# STM32ZET6.net
KiCad netlist of a schematic drawn in Altium Designer
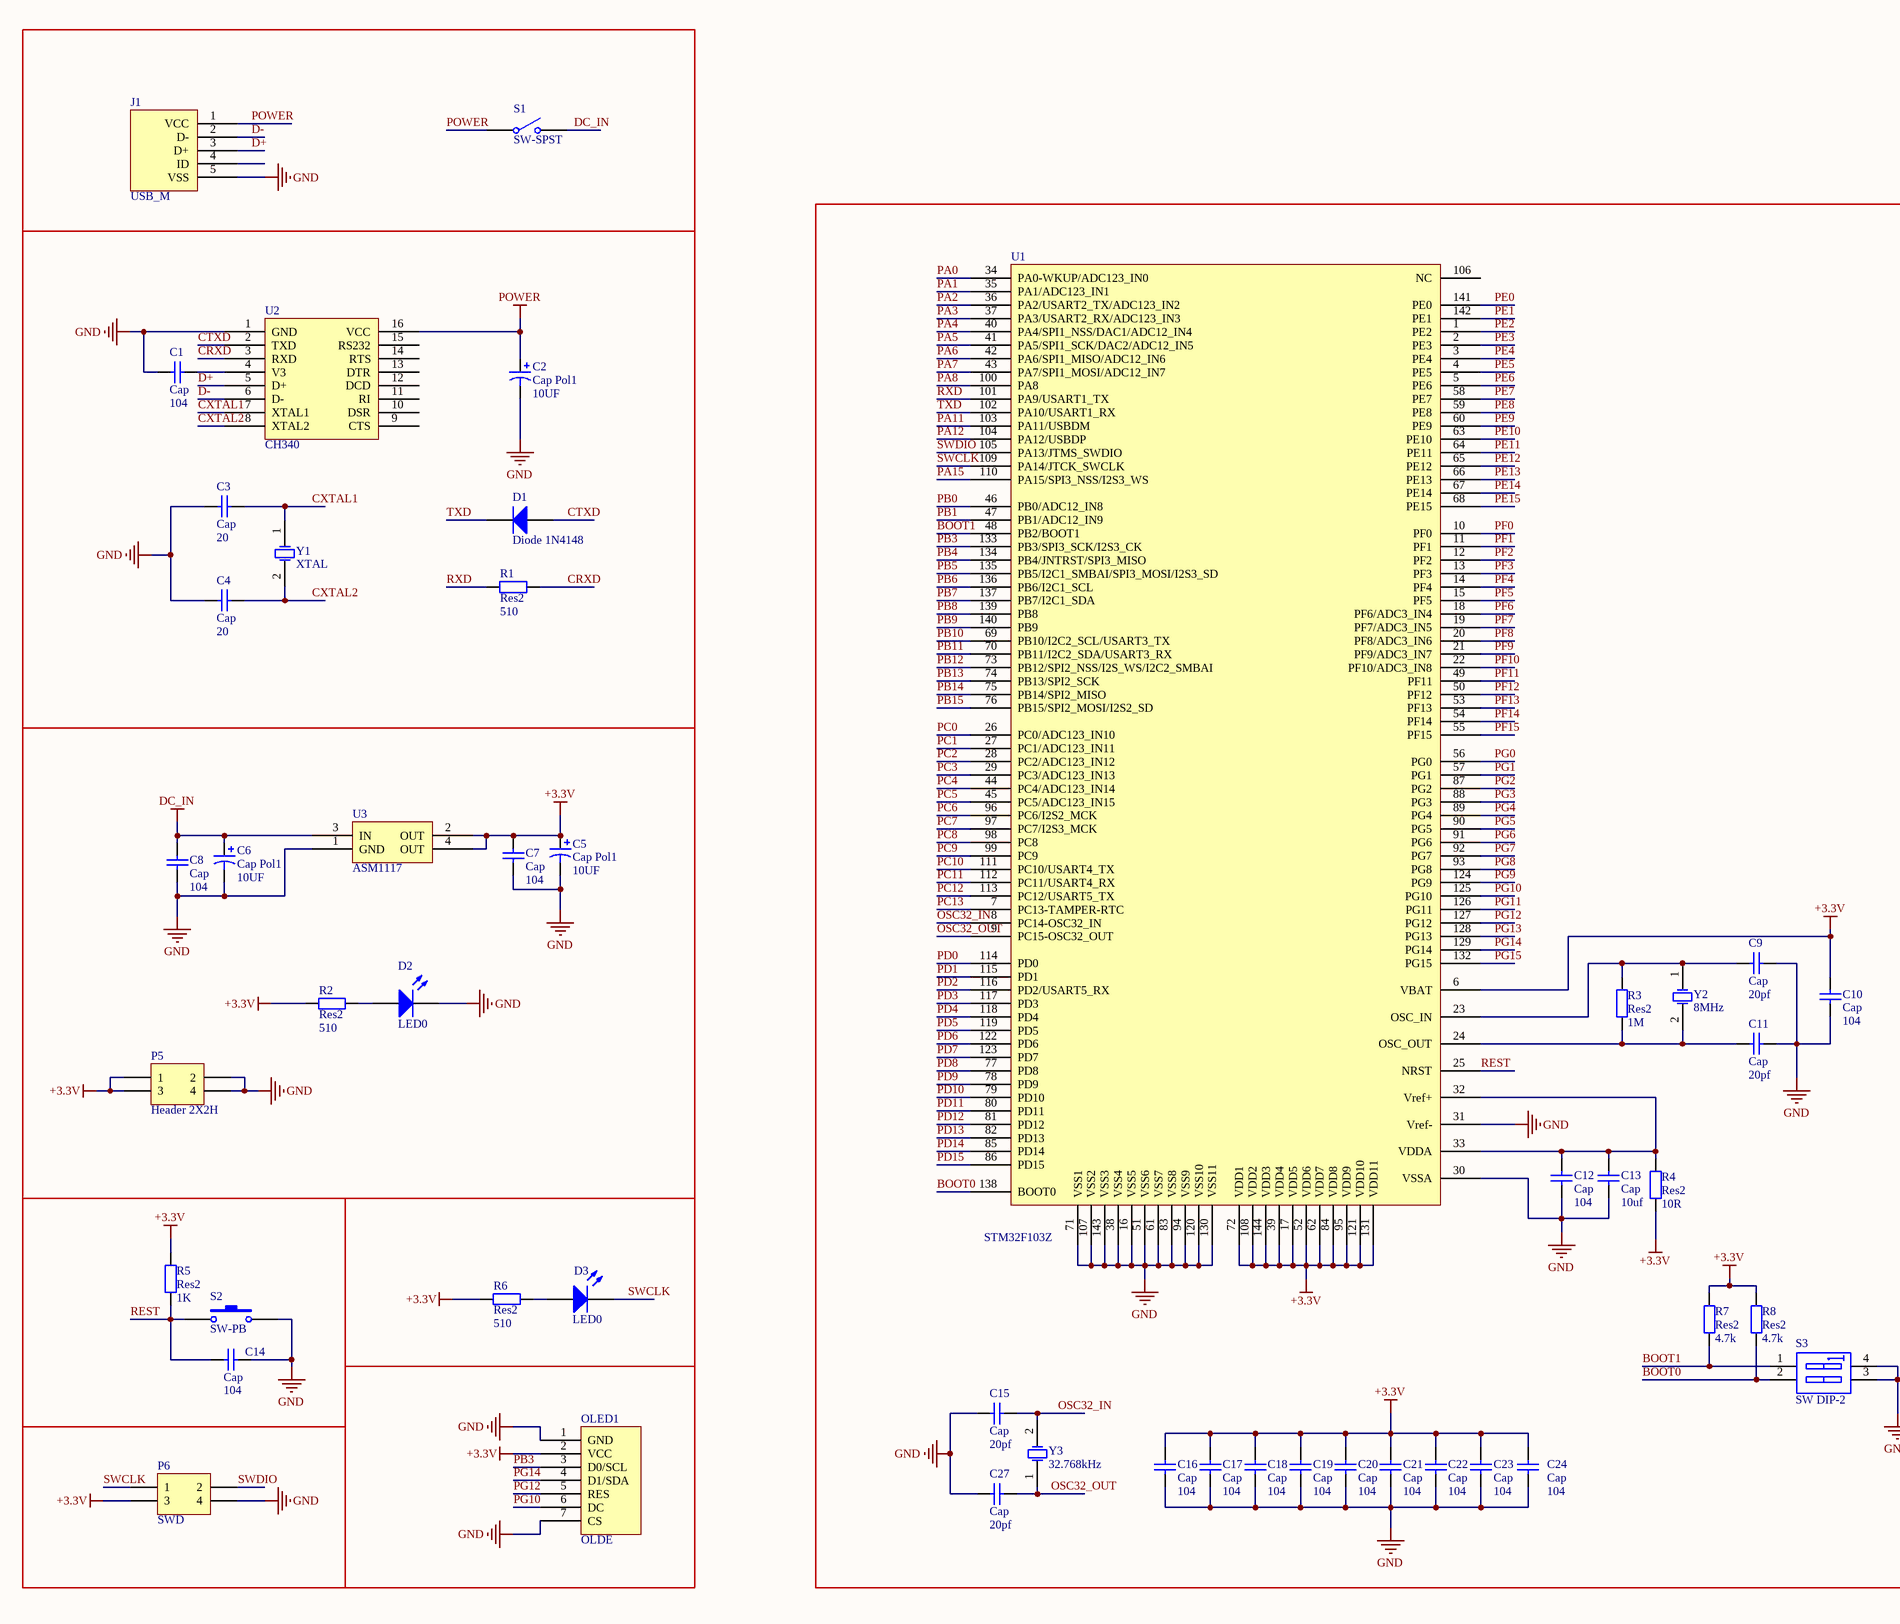
[diagram p0: STM32ZET6最小系统板.SchDoc, left]
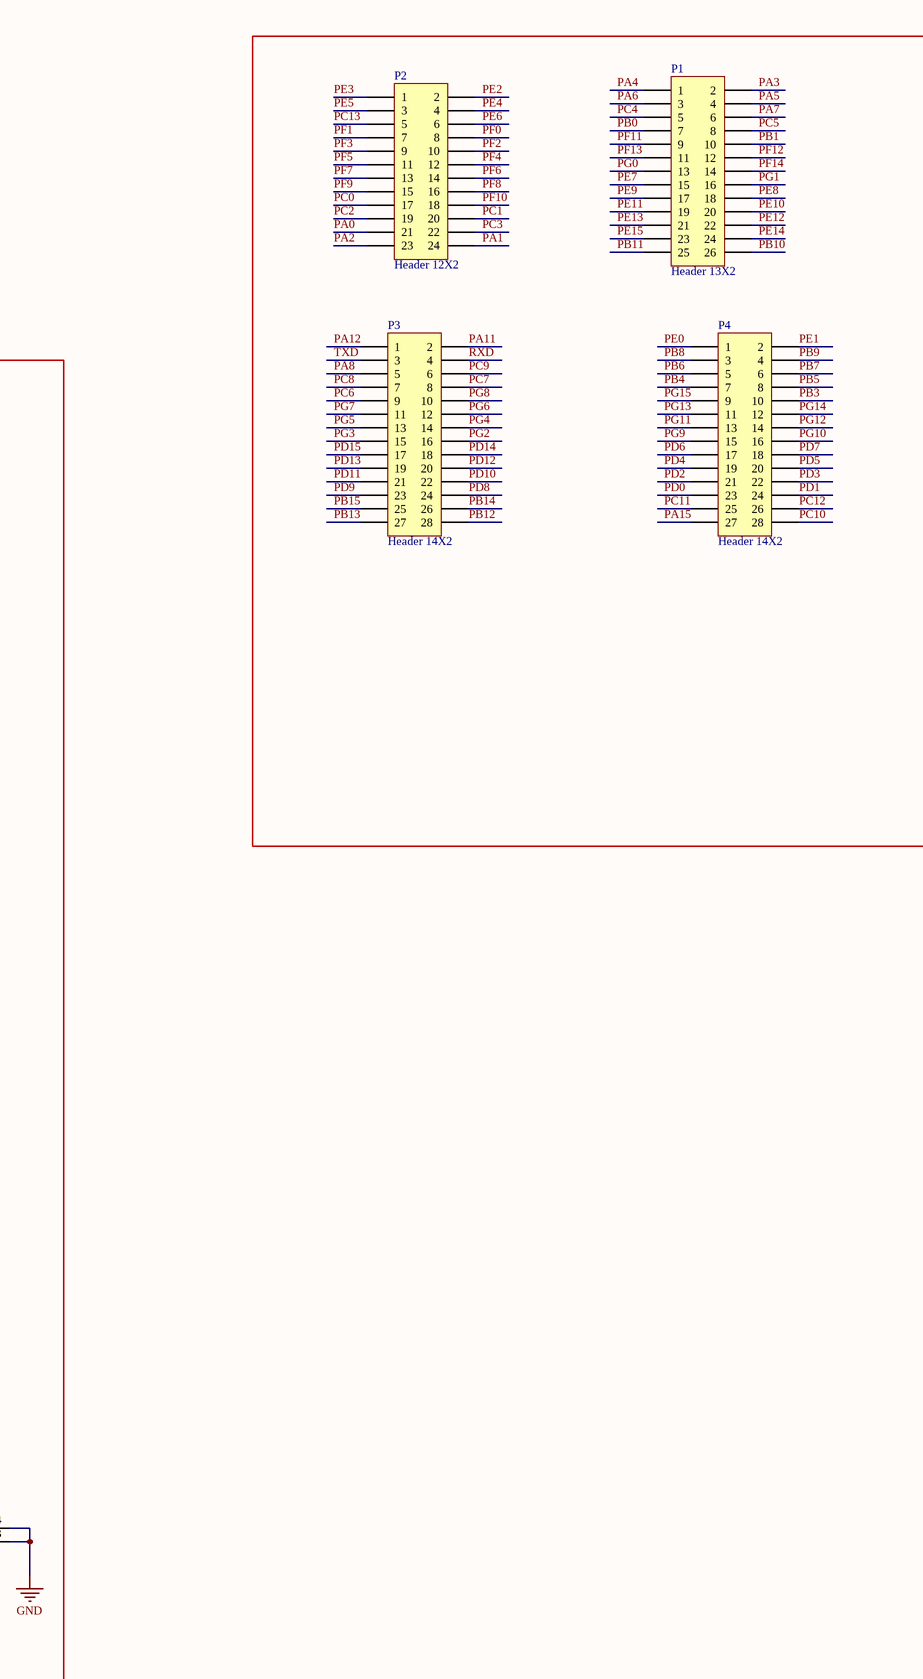
[diagram p1: STM32ZET6最小系统板.SchDoc, right]

(export (version "E")
  (design (tool "Eeschema 10.0.6"))
  (components
    (comp (ref "C1")
      (value "Cap")
      (footprint "C-0805")
      (description "Capacitor")
      (fields (field (name "ALTIUM_VALUE") "104") (field (name "PUBLISHER") "Altium Limited"))
      (libsource (lib "Miscellaneous Devices") (part "Cap"))
    )
    (comp (ref "C2")
      (value "Cap Pol1")
      (footprint "C1206")
      (description "Polarized Capacitor (Radial)")
      (fields (field (name "ALTIUM_VALUE") "10UF") (field (name "PUBLISHER") "Altium Limited"))
      (libsource (lib "Miscellaneous Devices") (part "Cap Pol1"))
    )
    (comp (ref "C3")
      (value "Cap")
      (footprint "C-0805")
      (description "Capacitor")
      (fields (field (name "ALTIUM_VALUE") "20") (field (name "PUBLISHER") "Altium Limited"))
      (libsource (lib "Miscellaneous Devices") (part "Cap"))
    )
    (comp (ref "C4")
      (value "Cap")
      (footprint "C-0805")
      (description "Capacitor")
      (fields (field (name "ALTIUM_VALUE") "20") (field (name "PUBLISHER") "Altium Limited"))
      (libsource (lib "Miscellaneous Devices") (part "Cap"))
    )
    (comp (ref "C5")
      (value "Cap Pol1")
      (footprint "C1206")
      (description "Polarized Capacitor (Radial)")
      (fields (field (name "ALTIUM_VALUE") "10UF") (field (name "PUBLISHER") "Altium Limited"))
      (libsource (lib "Miscellaneous Devices") (part "Cap Pol1"))
    )
    (comp (ref "C6")
      (value "Cap Pol1")
      (footprint "C1206")
      (description "Polarized Capacitor (Radial)")
      (fields (field (name "ALTIUM_VALUE") "10UF") (field (name "PUBLISHER") "Altium Limited"))
      (libsource (lib "Miscellaneous Devices") (part "Cap Pol1"))
    )
    (comp (ref "C7")
      (value "Cap")
      (footprint "C-0805")
      (description "Capacitor")
      (fields (field (name "ALTIUM_VALUE") "104") (field (name "PUBLISHER") "Altium Limited"))
      (libsource (lib "Miscellaneous Devices") (part "Cap"))
    )
    (comp (ref "C8")
      (value "Cap")
      (footprint "C-0805")
      (description "Capacitor")
      (fields (field (name "ALTIUM_VALUE") "104") (field (name "PUBLISHER") "Altium Limited"))
      (libsource (lib "Miscellaneous Devices") (part "Cap"))
    )
    (comp (ref "C9")
      (value "Cap")
      (footprint "C-0805")
      (description "Capacitor")
      (fields (field (name "ALTIUM_VALUE") "20pf") (field (name "PUBLISHER") "Altium Limited"))
      (libsource (lib "Miscellaneous Devices") (part "Cap"))
    )
    (comp (ref "C10")
      (value "Cap")
      (footprint "C-0805")
      (description "Capacitor")
      (fields (field (name "ALTIUM_VALUE") "104") (field (name "PUBLISHER") "Altium Limited"))
      (libsource (lib "Miscellaneous Devices") (part "Cap"))
    )
    (comp (ref "C11")
      (value "Cap")
      (footprint "C-0805")
      (description "Capacitor")
      (fields (field (name "ALTIUM_VALUE") "20pf") (field (name "PUBLISHER") "Altium Limited"))
      (libsource (lib "Miscellaneous Devices") (part "Cap"))
    )
    (comp (ref "C12")
      (value "Cap")
      (footprint "C-0805")
      (description "Capacitor")
      (fields (field (name "ALTIUM_VALUE") "104") (field (name "PUBLISHER") "Altium Limited"))
      (libsource (lib "Miscellaneous Devices") (part "Cap"))
    )
    (comp (ref "C13")
      (value "Cap")
      (footprint "C-0805")
      (description "Capacitor")
      (fields (field (name "ALTIUM_VALUE") "10uf") (field (name "PUBLISHER") "Altium Limited"))
      (libsource (lib "Miscellaneous Devices") (part "Cap"))
    )
    (comp (ref "C14")
      (value "Cap")
      (footprint "C-0805")
      (description "Capacitor")
      (fields (field (name "ALTIUM_VALUE") "104") (field (name "PUBLISHER") "Altium Limited"))
      (libsource (lib "Miscellaneous Devices") (part "Cap"))
    )
    (comp (ref "C15")
      (value "Cap")
      (footprint "C-0805")
      (description "Capacitor")
      (fields (field (name "ALTIUM_VALUE") "20pf") (field (name "PUBLISHER") "Altium Limited"))
      (libsource (lib "Miscellaneous Devices") (part "Cap"))
    )
    (comp (ref "C16")
      (value "Cap")
      (footprint "C-0805")
      (description "Capacitor")
      (fields (field (name "ALTIUM_VALUE") "104") (field (name "PUBLISHER") "Altium Limited"))
      (libsource (lib "Miscellaneous Devices") (part "Cap"))
    )
    (comp (ref "C17")
      (value "Cap")
      (footprint "C-0805")
      (description "Capacitor")
      (fields (field (name "ALTIUM_VALUE") "104") (field (name "PUBLISHER") "Altium Limited"))
      (libsource (lib "Miscellaneous Devices") (part "Cap"))
    )
    (comp (ref "C18")
      (value "Cap")
      (footprint "C-0805")
      (description "Capacitor")
      (fields (field (name "ALTIUM_VALUE") "104") (field (name "PUBLISHER") "Altium Limited"))
      (libsource (lib "Miscellaneous Devices") (part "Cap"))
    )
    (comp (ref "C19")
      (value "Cap")
      (footprint "C-0805")
      (description "Capacitor")
      (fields (field (name "ALTIUM_VALUE") "104") (field (name "PUBLISHER") "Altium Limited"))
      (libsource (lib "Miscellaneous Devices") (part "Cap"))
    )
    (comp (ref "C20")
      (value "Cap")
      (footprint "C-0805")
      (description "Capacitor")
      (fields (field (name "ALTIUM_VALUE") "104") (field (name "PUBLISHER") "Altium Limited"))
      (libsource (lib "Miscellaneous Devices") (part "Cap"))
    )
    (comp (ref "C21")
      (value "Cap")
      (footprint "C-0805")
      (description "Capacitor")
      (fields (field (name "ALTIUM_VALUE") "104") (field (name "PUBLISHER") "Altium Limited"))
      (libsource (lib "Miscellaneous Devices") (part "Cap"))
    )
    (comp (ref "C22")
      (value "Cap")
      (footprint "C-0805")
      (description "Capacitor")
      (fields (field (name "ALTIUM_VALUE") "104") (field (name "PUBLISHER") "Altium Limited"))
      (libsource (lib "Miscellaneous Devices") (part "Cap"))
    )
    (comp (ref "C23")
      (value "Cap")
      (footprint "C-0805")
      (description "Capacitor")
      (fields (field (name "ALTIUM_VALUE") "104") (field (name "PUBLISHER") "Altium Limited"))
      (libsource (lib "Miscellaneous Devices") (part "Cap"))
    )
    (comp (ref "C24")
      (value "Cap")
      (footprint "C-0805")
      (description "Capacitor")
      (fields (field (name "ALTIUM_VALUE") "104") (field (name "PUBLISHER") "Altium Limited"))
      (libsource (lib "Miscellaneous Devices") (part "Cap"))
    )
    (comp (ref "C27")
      (value "Cap")
      (footprint "C-0805")
      (description "Capacitor")
      (fields (field (name "ALTIUM_VALUE") "20pf") (field (name "PUBLISHER") "Altium Limited"))
      (libsource (lib "Miscellaneous Devices") (part "Cap"))
    )
    (comp (ref "D1")
      (value "Diode 1N4148")
      (footprint "SOT-123")
      (description "1 Amp General Purpose Rectifier")
      (fields (field (name "PUBLISHER") "Altium Limited"))
      (libsource (lib "Miscellaneous Devices") (part "Diode 1N4006"))
    )
    (comp (ref "D2")
      (value "LED0")
      (footprint "LED_0805")
      (description "Typical INFRARED GaAs LED")
      (fields (field (name "PUBLISHER") "Altium Limited"))
      (libsource (lib "Miscellaneous Devices") (part "LED0"))
    )
    (comp (ref "D3")
      (value "LED0")
      (footprint "LED_0805")
      (description "Typical INFRARED GaAs LED")
      (fields (field (name "PUBLISHER") "Altium Limited"))
      (libsource (lib "Miscellaneous Devices") (part "LED0"))
    )
    (comp (ref "J1")
      (value "USB_M")
      (footprint "USB_MICRO")
      (description "MicroUSB接口")
      (libsource (lib "常用封装") (part "USB_M"))
    )
    (comp (ref "OLED1") (value "OLDE") (footprint "HDR1X7") (libsource (lib "常用封装") (part "OLED-0.96寸")))
    (comp (ref "P1")
      (value "Header 13X2")
      (footprint "HDR2X13")
      (description "Header, 13-Pin, Dual row")
      (fields (field (name "PUBLISHER") "Altium Limited"))
      (libsource (lib "Miscellaneous Connectors") (part "Header 13X2"))
    )
    (comp (ref "P2")
      (value "Header 12X2")
      (footprint "HDR2X12")
      (description "Header, 12-Pin, Dual row")
      (fields (field (name "PUBLISHER") "Altium Limited"))
      (libsource (lib "Miscellaneous Connectors") (part "Header 12X2"))
    )
    (comp (ref "P3")
      (value "Header 14X2")
      (footprint "HDR2X14")
      (description "Header, 14-Pin, Dual row")
      (fields (field (name "PUBLISHER") "Altium Limited"))
      (libsource (lib "Miscellaneous Connectors") (part "Header 14X2"))
    )
    (comp (ref "P4")
      (value "Header 14X2")
      (footprint "HDR2X14")
      (description "Header, 14-Pin, Dual row")
      (fields (field (name "PUBLISHER") "Altium Limited"))
      (libsource (lib "Miscellaneous Connectors") (part "Header 14X2"))
    )
    (comp (ref "P5")
      (value "Header 2X2H")
      (footprint "HDR2X2")
      (description "Header, 2-Pin, Dual row, Right Angle")
      (fields (field (name "PUBLISHER") "Altium Limited"))
      (libsource (lib "Miscellaneous Connectors") (part "Header 2X2H"))
    )
    (comp (ref "P6")
      (value "SWD")
      (footprint "HDR2X2")
      (description "Header, 2-Pin, Dual row")
      (fields (field (name "PUBLISHER") "Altium Limited"))
      (libsource (lib "Miscellaneous Connectors") (part "Header 2X2"))
    )
    (comp (ref "R1")
      (value "Res2")
      (footprint "0805")
      (description "Resistor")
      (fields (field (name "ALTIUM_VALUE") "510") (field (name "PUBLISHER") "Altium Limited"))
      (libsource (lib "") (part "Res2_1"))
    )
    (comp (ref "R2")
      (value "Res2")
      (footprint "0805")
      (description "Resistor")
      (fields (field (name "ALTIUM_VALUE") "510") (field (name "PUBLISHER") "Altium Limited"))
      (libsource (lib "") (part "Res2_1"))
    )
    (comp (ref "R3")
      (value "Res2")
      (footprint "0805")
      (description "Resistor")
      (fields (field (name "ALTIUM_VALUE") "1M") (field (name "PUBLISHER") "Altium Limited"))
      (libsource (lib "Miscellaneous Devices") (part "Res2"))
    )
    (comp (ref "R4")
      (value "Res2")
      (footprint "0805")
      (description "Resistor")
      (fields (field (name "ALTIUM_VALUE") "10R") (field (name "PUBLISHER") "Altium Limited"))
      (libsource (lib "Miscellaneous Devices") (part "Res2"))
    )
    (comp (ref "R5")
      (value "Res2")
      (footprint "0805")
      (description "Resistor")
      (fields (field (name "ALTIUM_VALUE") "1K") (field (name "PUBLISHER") "Altium Limited"))
      (libsource (lib "Miscellaneous Devices") (part "Res2"))
    )
    (comp (ref "R6")
      (value "Res2")
      (footprint "0805")
      (description "Resistor")
      (fields (field (name "ALTIUM_VALUE") "510") (field (name "PUBLISHER") "Altium Limited"))
      (libsource (lib "") (part "Res2_1"))
    )
    (comp (ref "R7")
      (value "Res2")
      (footprint "0805")
      (description "Resistor")
      (fields (field (name "ALTIUM_VALUE") "4.7k") (field (name "PUBLISHER") "Altium Limited"))
      (libsource (lib "Miscellaneous Devices") (part "Res2"))
    )
    (comp (ref "R8")
      (value "Res2")
      (footprint "0805")
      (description "Resistor")
      (fields (field (name "ALTIUM_VALUE") "4.7k") (field (name "PUBLISHER") "Altium Limited"))
      (libsource (lib "Miscellaneous Devices") (part "Res2"))
    )
    (comp (ref "S1")
      (value "SW-SPST")
      (footprint "SW-mini-6pin")
      (description "Single-Pole, Single-Throw Switch")
      (fields (field (name "PUBLISHER") "Altium Limited"))
      (libsource (lib "Miscellaneous Devices") (part "SW-SPST"))
    )
    (comp (ref "S2")
      (value "SW-PB")
      (footprint "贴片开关")
      (description "Switch")
      (fields (field (name "PUBLISHER") "Altium Limited"))
      (libsource (lib "Miscellaneous Devices") (part "SW-PB"))
    )
    (comp (ref "S3")
      (value "SW DIP-2")
      (footprint "SW4_2BIT")
      (description "编码开关")
      (fields (field (name "PUBLISHER") "Altium Limited"))
      (libsource (lib "常用封装") (part "SW DIP-2"))
    )
    (comp (ref "U1")
      (value "STM32F103Z")
      (footprint "TQFP144_N")
      (description "STM32单片机144引脚")
      (libsource (lib "常用封装") (part "STM32F103Z"))
    )
    (comp (ref "U2") (value "CH340") (footprint "SO-16") (libsource (lib "常用封装") (part "CH340")))
    (comp (ref "U3")
      (value "ASM1117")
      (footprint "SOT-223")
      (description "3.3V稳压芯片")
      (libsource (lib "常用封装") (part "ASM1117"))
    )
    (comp (ref "Y1")
      (value "XTAL")
      (footprint "XTAL-HCM49")
      (description "Crystal Oscillator")
      (fields (field (name "PUBLISHER") "Altium Limited"))
      (libsource (lib "Miscellaneous Devices") (part "XTAL"))
    )
    (comp (ref "Y2")
      (value "8MHz")
      (footprint "XTAL-HCM49")
      (description "Crystal Oscillator")
      (fields (field (name "PUBLISHER") "Altium Limited"))
      (libsource (lib "Miscellaneous Devices") (part "XTAL"))
    )
    (comp (ref "Y3")
      (value "32.768kHz")
      (footprint "X-TC")
      (description "Crystal Oscillator")
      (fields (field (name "PUBLISHER") "Altium Limited"))
      (libsource (lib "Miscellaneous Devices") (part "XTAL"))
    )
  )
  (nets
    (net (code "1") (name "+3.3V") (class "Default")
      (node (ref "C10") (pin "2") (pinfunction "2_2") (pintype "passive"))
      (node (ref "C16") (pin "2") (pinfunction "2_2") (pintype "passive"))
      (node (ref "C17") (pin "2") (pinfunction "2_2") (pintype "passive"))
      (node (ref "C18") (pin "2") (pinfunction "2_2") (pintype "passive"))
      (node (ref "C19") (pin "2") (pinfunction "2_2") (pintype "passive"))
      (node (ref "C20") (pin "2") (pinfunction "2_2") (pintype "passive"))
      (node (ref "C21") (pin "2") (pinfunction "2_2") (pintype "passive"))
      (node (ref "C22") (pin "2") (pinfunction "2_2") (pintype "passive"))
      (node (ref "C23") (pin "2") (pinfunction "2_2") (pintype "passive"))
      (node (ref "C24") (pin "2") (pinfunction "2_2") (pintype "passive"))
      (node (ref "C5") (pin "1") (pinfunction "1_1") (pintype "passive"))
      (node (ref "C7") (pin "2") (pinfunction "2_2") (pintype "passive"))
      (node (ref "OLED1") (pin "2") (pinfunction "VCC_2") (pintype "passive"))
      (node (ref "P5") (pin "1") (pinfunction "1_1") (pintype "passive"))
      (node (ref "P5") (pin "3") (pinfunction "3_3") (pintype "passive"))
      (node (ref "P6") (pin "3") (pinfunction "3_3") (pintype "passive"))
      (node (ref "R2") (pin "1") (pinfunction "1_1") (pintype "passive"))
      (node (ref "R4") (pin "1") (pinfunction "1_1") (pintype "passive"))
      (node (ref "R5") (pin "2") (pinfunction "2_2") (pintype "passive"))
      (node (ref "R6") (pin "1") (pinfunction "1_1") (pintype "passive"))
      (node (ref "R7") (pin "2") (pinfunction "2_2") (pintype "passive"))
      (node (ref "R8") (pin "2") (pinfunction "2_2") (pintype "passive"))
      (node (ref "U1") (pin "108") (pinfunction "VDD2_108") (pintype "passive"))
      (node (ref "U1") (pin "121") (pinfunction "VDD10_121") (pintype "passive"))
      (node (ref "U1") (pin "131") (pinfunction "VDD11_131") (pintype "passive"))
      (node (ref "U1") (pin "144") (pinfunction "VDD3_144") (pintype "passive"))
      (node (ref "U1") (pin "17") (pinfunction "VDD5_17") (pintype "passive"))
      (node (ref "U1") (pin "39") (pinfunction "VDD4_39") (pintype "passive"))
      (node (ref "U1") (pin "52") (pinfunction "VDD6_52") (pintype "passive"))
      (node (ref "U1") (pin "6") (pinfunction "VBAT_6") (pintype "passive"))
      (node (ref "U1") (pin "62") (pinfunction "VDD7_62") (pintype "passive"))
      (node (ref "U1") (pin "72") (pinfunction "VDD1_72") (pintype "passive"))
      (node (ref "U1") (pin "84") (pinfunction "VDD8_84") (pintype "passive"))
      (node (ref "U1") (pin "95") (pinfunction "VDD9_95") (pintype "passive"))
      (node (ref "U3") (pin "2") (pinfunction "OUT_2") (pintype "passive"))
      (node (ref "U3") (pin "4") (pinfunction "OUT_4") (pintype "passive"))
    )
    (net (code "2") (name "/BOOT0") (class "Default")
      (node (ref "R8") (pin "1") (pinfunction "1_1") (pintype "passive"))
      (node (ref "S3") (pin "2") (pinfunction "A2_2") (pintype "passive"))
      (node (ref "U1") (pin "138") (pinfunction "BOOT0_138") (pintype "passive"))
    )
    (net (code "3") (name "/BOOT1") (class "Default")
      (node (ref "R7") (pin "1") (pinfunction "1_1") (pintype "passive"))
      (node (ref "S3") (pin "1") (pinfunction "A1_1") (pintype "passive"))
      (node (ref "U1") (pin "48") (pinfunction "PB2/BOOT1_48") (pintype "passive"))
    )
    (net (code "4") (name "/CRXD") (class "Default")
      (node (ref "R1") (pin "2") (pinfunction "2_2") (pintype "passive"))
      (node (ref "U2") (pin "3") (pinfunction "RXD_3") (pintype "passive"))
    )
    (net (code "5") (name "/CTXD") (class "Default")
      (node (ref "D1") (pin "1") (pinfunction "A_1") (pintype "passive"))
      (node (ref "U2") (pin "2") (pinfunction "TXD_2") (pintype "passive"))
    )
    (net (code "6") (name "/CXTAL1") (class "Default")
      (node (ref "C3") (pin "1") (pinfunction "1_1") (pintype "passive"))
      (node (ref "U2") (pin "7") (pinfunction "XTAL1_7") (pintype "passive"))
      (node (ref "Y1") (pin "1") (pinfunction "OSC1_1") (pintype "passive"))
    )
    (net (code "7") (name "/CXTAL2") (class "Default")
      (node (ref "C4") (pin "1") (pinfunction "1_1") (pintype "passive"))
      (node (ref "U2") (pin "8") (pinfunction "XTAL2_8") (pintype "passive"))
      (node (ref "Y1") (pin "2") (pinfunction "OSC2_2") (pintype "passive"))
    )
    (net (code "8") (name "/D+") (class "Default")
      (node (ref "J1") (pin "3") (pinfunction "D+_3") (pintype "passive"))
      (node (ref "U2") (pin "5") (pinfunction "D+_5") (pintype "passive"))
    )
    (net (code "9") (name "/D-") (class "Default")
      (node (ref "J1") (pin "2") (pinfunction "D-_2") (pintype "passive"))
      (node (ref "U2") (pin "6") (pinfunction "D-_6") (pintype "passive"))
    )
    (net (code "10") (name "/OSC32_IN") (class "Default")
      (node (ref "C15") (pin "2") (pinfunction "2_2") (pintype "passive"))
      (node (ref "U1") (pin "8") (pinfunction "PC14-OSC32_IN_8") (pintype "passive"))
      (node (ref "Y3") (pin "2") (pinfunction "OSC2_2") (pintype "passive"))
    )
    (net (code "11") (name "/OSC32_OUT") (class "Default")
      (node (ref "C27") (pin "2") (pinfunction "2_2") (pintype "passive"))
      (node (ref "U1") (pin "9") (pinfunction "PC15-OSC32_OUT_9") (pintype "passive"))
      (node (ref "Y3") (pin "1") (pinfunction "OSC1_1") (pintype "passive"))
    )
    (net (code "12") (name "/PA0") (class "Default")
      (node (ref "P2") (pin "21") (pinfunction "21_21") (pintype "passive"))
      (node (ref "U1") (pin "34") (pinfunction "PA0-WKUP/ADC123_IN0_34") (pintype "passive"))
    )
    (net (code "13") (name "/PA1") (class "Default")
      (node (ref "P2") (pin "24") (pinfunction "24_24") (pintype "passive"))
      (node (ref "U1") (pin "35") (pinfunction "PA1/ADC123_IN1_35") (pintype "passive"))
    )
    (net (code "14") (name "/PA2") (class "Default")
      (node (ref "P2") (pin "23") (pinfunction "23_23") (pintype "passive"))
      (node (ref "U1") (pin "36") (pinfunction "PA2/USART2_TX/ADC123_IN2_36") (pintype "passive"))
    )
    (net (code "15") (name "/PA3") (class "Default")
      (node (ref "P1") (pin "2") (pinfunction "2_2") (pintype "passive"))
      (node (ref "U1") (pin "37") (pinfunction "PA3/USART2_RX/ADC123_IN3_37") (pintype "passive"))
    )
    (net (code "16") (name "/PA4") (class "Default")
      (node (ref "P1") (pin "1") (pinfunction "1_1") (pintype "passive"))
      (node (ref "U1") (pin "40") (pinfunction "PA4/SPI1_NSS/DAC1/ADC12_IN4_40") (pintype "passive"))
    )
    (net (code "17") (name "/PA5") (class "Default")
      (node (ref "P1") (pin "4") (pinfunction "4_4") (pintype "passive"))
      (node (ref "U1") (pin "41") (pinfunction "PA5/SPI1_SCK/DAC2/ADC12_IN5_41") (pintype "passive"))
    )
    (net (code "18") (name "/PA6") (class "Default")
      (node (ref "P1") (pin "3") (pinfunction "3_3") (pintype "passive"))
      (node (ref "U1") (pin "42") (pinfunction "PA6/SPI1_MISO/ADC12_IN6_42") (pintype "passive"))
    )
    (net (code "19") (name "/PA7") (class "Default")
      (node (ref "P1") (pin "6") (pinfunction "6_6") (pintype "passive"))
      (node (ref "U1") (pin "43") (pinfunction "PA7/SPI1_MOSI/ADC12_IN7_43") (pintype "passive"))
    )
    (net (code "20") (name "/PA8") (class "Default")
      (node (ref "P3") (pin "5") (pinfunction "5_5") (pintype "passive"))
      (node (ref "U1") (pin "100") (pinfunction "PA8_100") (pintype "passive"))
    )
    (net (code "21") (name "/PA11") (class "Default")
      (node (ref "P3") (pin "2") (pinfunction "2_2") (pintype "passive"))
      (node (ref "U1") (pin "103") (pinfunction "PA11/USBDM_103") (pintype "passive"))
    )
    (net (code "22") (name "/PA12") (class "Default")
      (node (ref "P3") (pin "1") (pinfunction "1_1") (pintype "passive"))
      (node (ref "U1") (pin "104") (pinfunction "PA12/USBDP_104") (pintype "passive"))
    )
    (net (code "23") (name "/PA15") (class "Default")
      (node (ref "P4") (pin "27") (pinfunction "27_27") (pintype "passive"))
      (node (ref "U1") (pin "110") (pinfunction "PA15/SPI3_NSS/I2S3_WS_110") (pintype "passive"))
    )
    (net (code "24") (name "/PB0") (class "Default")
      (node (ref "P1") (pin "7") (pinfunction "7_7") (pintype "passive"))
      (node (ref "U1") (pin "46") (pinfunction "PB0/ADC12_IN8_46") (pintype "passive"))
    )
    (net (code "25") (name "/PB1") (class "Default")
      (node (ref "P1") (pin "10") (pinfunction "10_10") (pintype "passive"))
      (node (ref "U1") (pin "47") (pinfunction "PB1/ADC12_IN9_47") (pintype "passive"))
    )
    (net (code "26") (name "/PB3") (class "Default")
      (node (ref "OLED1") (pin "3") (pinfunction "D0/SCL_3") (pintype "passive"))
      (node (ref "P4") (pin "10") (pinfunction "10_10") (pintype "passive"))
      (node (ref "U1") (pin "133") (pinfunction "PB3/SPI3_SCK/I2S3_CK_133") (pintype "passive"))
    )
    (net (code "27") (name "/PB4") (class "Default")
      (node (ref "P4") (pin "7") (pinfunction "7_7") (pintype "passive"))
      (node (ref "U1") (pin "134") (pinfunction "PB4/JNTRST/SPI3_MISO_134") (pintype "passive"))
    )
    (net (code "28") (name "/PB5") (class "Default")
      (node (ref "P4") (pin "8") (pinfunction "8_8") (pintype "passive"))
      (node (ref "U1") (pin "135") (pinfunction "PB5/I2C1_SMBAI/SPI3_MOSI/I2S3_SD_135") (pintype "passive"))
    )
    (net (code "29") (name "/PB6") (class "Default")
      (node (ref "P4") (pin "5") (pinfunction "5_5") (pintype "passive"))
      (node (ref "U1") (pin "136") (pinfunction "PB6/I2C1_SCL_136") (pintype "passive"))
    )
    (net (code "30") (name "/PB7") (class "Default")
      (node (ref "P4") (pin "6") (pinfunction "6_6") (pintype "passive"))
      (node (ref "U1") (pin "137") (pinfunction "PB7/I2C1_SDA_137") (pintype "passive"))
    )
    (net (code "31") (name "/PB8") (class "Default")
      (node (ref "P4") (pin "3") (pinfunction "3_3") (pintype "passive"))
      (node (ref "U1") (pin "139") (pinfunction "PB8_139") (pintype "passive"))
    )
    (net (code "32") (name "/PB9") (class "Default")
      (node (ref "P4") (pin "4") (pinfunction "4_4") (pintype "passive"))
      (node (ref "U1") (pin "140") (pinfunction "PB9_140") (pintype "passive"))
    )
    (net (code "33") (name "/PB10") (class "Default")
      (node (ref "P1") (pin "26") (pinfunction "26_26") (pintype "passive"))
      (node (ref "U1") (pin "69") (pinfunction "PB10/I2C2_SCL/USART3_TX_69") (pintype "passive"))
    )
    (net (code "34") (name "/PB11") (class "Default")
      (node (ref "P1") (pin "25") (pinfunction "25_25") (pintype "passive"))
      (node (ref "U1") (pin "70") (pinfunction "PB11/I2C2_SDA/USART3_RX_70") (pintype "passive"))
    )
    (net (code "35") (name "/PB12") (class "Default")
      (node (ref "P3") (pin "28") (pinfunction "28_28") (pintype "passive"))
      (node (ref "U1") (pin "73") (pinfunction "PB12/SPI2_NSS/I2S_WS/I2C2_SMBAI_73") (pintype "passive"))
    )
    (net (code "36") (name "/PB13") (class "Default")
      (node (ref "P3") (pin "27") (pinfunction "27_27") (pintype "passive"))
      (node (ref "U1") (pin "74") (pinfunction "PB13/SPI2_SCK_74") (pintype "passive"))
    )
    (net (code "37") (name "/PB14") (class "Default")
      (node (ref "P3") (pin "26") (pinfunction "26_26") (pintype "passive"))
      (node (ref "U1") (pin "75") (pinfunction "PB14/SPI2_MISO_75") (pintype "passive"))
    )
    (net (code "38") (name "/PB15") (class "Default")
      (node (ref "P3") (pin "25") (pinfunction "25_25") (pintype "passive"))
      (node (ref "U1") (pin "76") (pinfunction "PB15/SPI2_MOSI/I2S2_SD_76") (pintype "passive"))
    )
    (net (code "39") (name "/PC0") (class "Default")
      (node (ref "P2") (pin "17") (pinfunction "17_17") (pintype "passive"))
      (node (ref "U1") (pin "26") (pinfunction "PC0/ADC123_IN10_26") (pintype "passive"))
    )
    (net (code "40") (name "/PC1") (class "Default")
      (node (ref "P2") (pin "20") (pinfunction "20_20") (pintype "passive"))
      (node (ref "U1") (pin "27") (pinfunction "PC1/ADC123_IN11_27") (pintype "passive"))
    )
    (net (code "41") (name "/PC2") (class "Default")
      (node (ref "P2") (pin "19") (pinfunction "19_19") (pintype "passive"))
      (node (ref "U1") (pin "28") (pinfunction "PC2/ADC123_IN12_28") (pintype "passive"))
    )
    (net (code "42") (name "/PC3") (class "Default")
      (node (ref "P2") (pin "22") (pinfunction "22_22") (pintype "passive"))
      (node (ref "U1") (pin "29") (pinfunction "PC3/ADC123_IN13_29") (pintype "passive"))
    )
    (net (code "43") (name "/PC4") (class "Default")
      (node (ref "P1") (pin "5") (pinfunction "5_5") (pintype "passive"))
      (node (ref "U1") (pin "44") (pinfunction "PC4/ADC123_IN14_44") (pintype "passive"))
    )
    (net (code "44") (name "/PC5") (class "Default")
      (node (ref "P1") (pin "8") (pinfunction "8_8") (pintype "passive"))
      (node (ref "U1") (pin "45") (pinfunction "PC5/ADC123_IN15_45") (pintype "passive"))
    )
    (net (code "45") (name "/PC6") (class "Default")
      (node (ref "P3") (pin "9") (pinfunction "9_9") (pintype "passive"))
      (node (ref "U1") (pin "96") (pinfunction "PC6/I2S2_MCK_96") (pintype "passive"))
    )
    (net (code "46") (name "/PC7") (class "Default")
      (node (ref "P3") (pin "8") (pinfunction "8_8") (pintype "passive"))
      (node (ref "U1") (pin "97") (pinfunction "PC7/I2S3_MCK_97") (pintype "passive"))
    )
    (net (code "47") (name "/PC8") (class "Default")
      (node (ref "P3") (pin "7") (pinfunction "7_7") (pintype "passive"))
      (node (ref "U1") (pin "98") (pinfunction "PC8_98") (pintype "passive"))
    )
    (net (code "48") (name "/PC9") (class "Default")
      (node (ref "P3") (pin "6") (pinfunction "6_6") (pintype "passive"))
      (node (ref "U1") (pin "99") (pinfunction "PC9_99") (pintype "passive"))
    )
    (net (code "49") (name "/PC10") (class "Default")
      (node (ref "P4") (pin "28") (pinfunction "28_28") (pintype "passive"))
      (node (ref "U1") (pin "111") (pinfunction "PC10/USART4_TX_111") (pintype "passive"))
    )
    (net (code "50") (name "/PC11") (class "Default")
      (node (ref "P4") (pin "25") (pinfunction "25_25") (pintype "passive"))
      (node (ref "U1") (pin "112") (pinfunction "PC11/USART4_RX_112") (pintype "passive"))
    )
    (net (code "51") (name "/PC12") (class "Default")
      (node (ref "P4") (pin "26") (pinfunction "26_26") (pintype "passive"))
      (node (ref "U1") (pin "113") (pinfunction "PC12/USART5_TX_113") (pintype "passive"))
    )
    (net (code "52") (name "/PC13") (class "Default")
      (node (ref "P2") (pin "5") (pinfunction "5_5") (pintype "passive"))
      (node (ref "U1") (pin "7") (pinfunction "PC13-TAMPER-RTC_7") (pintype "passive"))
    )
    (net (code "53") (name "/PD0") (class "Default")
      (node (ref "P4") (pin "23") (pinfunction "23_23") (pintype "passive"))
      (node (ref "U1") (pin "114") (pinfunction "PD0_114") (pintype "passive"))
    )
    (net (code "54") (name "/PD1") (class "Default")
      (node (ref "P4") (pin "24") (pinfunction "24_24") (pintype "passive"))
      (node (ref "U1") (pin "115") (pinfunction "PD1_115") (pintype "passive"))
    )
    (net (code "55") (name "/PD2") (class "Default")
      (node (ref "P4") (pin "21") (pinfunction "21_21") (pintype "passive"))
      (node (ref "U1") (pin "116") (pinfunction "PD2/USART5_RX_116") (pintype "passive"))
    )
    (net (code "56") (name "/PD3") (class "Default")
      (node (ref "P4") (pin "22") (pinfunction "22_22") (pintype "passive"))
      (node (ref "U1") (pin "117") (pinfunction "PD3_117") (pintype "passive"))
    )
    (net (code "57") (name "/PD4") (class "Default")
      (node (ref "P4") (pin "19") (pinfunction "19_19") (pintype "passive"))
      (node (ref "U1") (pin "118") (pinfunction "PD4_118") (pintype "passive"))
    )
    (net (code "58") (name "/PD5") (class "Default")
      (node (ref "P4") (pin "20") (pinfunction "20_20") (pintype "passive"))
      (node (ref "U1") (pin "119") (pinfunction "PD5_119") (pintype "passive"))
    )
    (net (code "59") (name "/PD6") (class "Default")
      (node (ref "P4") (pin "17") (pinfunction "17_17") (pintype "passive"))
      (node (ref "U1") (pin "122") (pinfunction "PD6_122") (pintype "passive"))
    )
    (net (code "60") (name "/PD7") (class "Default")
      (node (ref "P4") (pin "18") (pinfunction "18_18") (pintype "passive"))
      (node (ref "U1") (pin "123") (pinfunction "PD7_123") (pintype "passive"))
    )
    (net (code "61") (name "/PD8") (class "Default")
      (node (ref "P3") (pin "24") (pinfunction "24_24") (pintype "passive"))
      (node (ref "U1") (pin "77") (pinfunction "PD8_77") (pintype "passive"))
    )
    (net (code "62") (name "/PD9") (class "Default")
      (node (ref "P3") (pin "23") (pinfunction "23_23") (pintype "passive"))
      (node (ref "U1") (pin "78") (pinfunction "PD9_78") (pintype "passive"))
    )
    (net (code "63") (name "/PD10") (class "Default")
      (node (ref "P3") (pin "22") (pinfunction "22_22") (pintype "passive"))
      (node (ref "U1") (pin "79") (pinfunction "PD10_79") (pintype "passive"))
    )
    (net (code "64") (name "/PD11") (class "Default")
      (node (ref "P3") (pin "21") (pinfunction "21_21") (pintype "passive"))
      (node (ref "U1") (pin "80") (pinfunction "PD11_80") (pintype "passive"))
    )
    (net (code "65") (name "/PD12") (class "Default")
      (node (ref "P3") (pin "20") (pinfunction "20_20") (pintype "passive"))
      (node (ref "U1") (pin "81") (pinfunction "PD12_81") (pintype "passive"))
    )
    (net (code "66") (name "/PD13") (class "Default")
      (node (ref "P3") (pin "19") (pinfunction "19_19") (pintype "passive"))
      (node (ref "U1") (pin "82") (pinfunction "PD13_82") (pintype "passive"))
    )
    (net (code "67") (name "/PD14") (class "Default")
      (node (ref "P3") (pin "18") (pinfunction "18_18") (pintype "passive"))
      (node (ref "U1") (pin "85") (pinfunction "PD14_85") (pintype "passive"))
    )
    (net (code "68") (name "/PD15") (class "Default")
      (node (ref "P3") (pin "17") (pinfunction "17_17") (pintype "passive"))
      (node (ref "U1") (pin "86") (pinfunction "PD15_86") (pintype "passive"))
    )
    (net (code "69") (name "/PE0") (class "Default")
      (node (ref "P4") (pin "1") (pinfunction "1_1") (pintype "passive"))
      (node (ref "U1") (pin "141") (pinfunction "PE0_141") (pintype "passive"))
    )
    (net (code "70") (name "/PE1") (class "Default")
      (node (ref "P4") (pin "2") (pinfunction "2_2") (pintype "passive"))
      (node (ref "U1") (pin "142") (pinfunction "PE1_142") (pintype "passive"))
    )
    (net (code "71") (name "/PE2") (class "Default")
      (node (ref "P2") (pin "2") (pinfunction "2_2") (pintype "passive"))
      (node (ref "U1") (pin "1") (pinfunction "PE2_1") (pintype "passive"))
    )
    (net (code "72") (name "/PE3") (class "Default")
      (node (ref "P2") (pin "1") (pinfunction "1_1") (pintype "passive"))
      (node (ref "U1") (pin "2") (pinfunction "PE3_2") (pintype "passive"))
    )
    (net (code "73") (name "/PE4") (class "Default")
      (node (ref "P2") (pin "4") (pinfunction "4_4") (pintype "passive"))
      (node (ref "U1") (pin "3") (pinfunction "PE4_3") (pintype "passive"))
    )
    (net (code "74") (name "/PE5") (class "Default")
      (node (ref "P2") (pin "3") (pinfunction "3_3") (pintype "passive"))
      (node (ref "U1") (pin "4") (pinfunction "PE5_4") (pintype "passive"))
    )
    (net (code "75") (name "/PE6") (class "Default")
      (node (ref "P2") (pin "6") (pinfunction "6_6") (pintype "passive"))
      (node (ref "U1") (pin "5") (pinfunction "PE6_5") (pintype "passive"))
    )
    (net (code "76") (name "/PE7") (class "Default")
      (node (ref "P1") (pin "15") (pinfunction "15_15") (pintype "passive"))
      (node (ref "U1") (pin "58") (pinfunction "PE7_58") (pintype "passive"))
    )
    (net (code "77") (name "/PE8") (class "Default")
      (node (ref "P1") (pin "18") (pinfunction "18_18") (pintype "passive"))
      (node (ref "U1") (pin "59") (pinfunction "PE8_59") (pintype "passive"))
    )
    (net (code "78") (name "/PE9") (class "Default")
      (node (ref "P1") (pin "17") (pinfunction "17_17") (pintype "passive"))
      (node (ref "U1") (pin "60") (pinfunction "PE9_60") (pintype "passive"))
    )
    (net (code "79") (name "/PE10") (class "Default")
      (node (ref "P1") (pin "20") (pinfunction "20_20") (pintype "passive"))
      (node (ref "U1") (pin "63") (pinfunction "PE10_63") (pintype "passive"))
    )
    (net (code "80") (name "/PE11") (class "Default")
      (node (ref "P1") (pin "19") (pinfunction "19_19") (pintype "passive"))
      (node (ref "U1") (pin "64") (pinfunction "PE11_64") (pintype "passive"))
    )
    (net (code "81") (name "/PE12") (class "Default")
      (node (ref "P1") (pin "22") (pinfunction "22_22") (pintype "passive"))
      (node (ref "U1") (pin "65") (pinfunction "PE12_65") (pintype "passive"))
    )
    (net (code "82") (name "/PE13") (class "Default")
      (node (ref "P1") (pin "21") (pinfunction "21_21") (pintype "passive"))
      (node (ref "U1") (pin "66") (pinfunction "PE13_66") (pintype "passive"))
    )
    (net (code "83") (name "/PE14") (class "Default")
      (node (ref "P1") (pin "24") (pinfunction "24_24") (pintype "passive"))
      (node (ref "U1") (pin "67") (pinfunction "PE14_67") (pintype "passive"))
    )
    (net (code "84") (name "/PE15") (class "Default")
      (node (ref "P1") (pin "23") (pinfunction "23_23") (pintype "passive"))
      (node (ref "U1") (pin "68") (pinfunction "PE15_68") (pintype "passive"))
    )
    (net (code "85") (name "/PF0") (class "Default")
      (node (ref "P2") (pin "8") (pinfunction "8_8") (pintype "passive"))
      (node (ref "U1") (pin "10") (pinfunction "PF0_10") (pintype "passive"))
    )
    (net (code "86") (name "/PF1") (class "Default")
      (node (ref "P2") (pin "7") (pinfunction "7_7") (pintype "passive"))
      (node (ref "U1") (pin "11") (pinfunction "PF1_11") (pintype "passive"))
    )
    (net (code "87") (name "/PF2") (class "Default")
      (node (ref "P2") (pin "10") (pinfunction "10_10") (pintype "passive"))
      (node (ref "U1") (pin "12") (pinfunction "PF2_12") (pintype "passive"))
    )
    (net (code "88") (name "/PF3") (class "Default")
      (node (ref "P2") (pin "9") (pinfunction "9_9") (pintype "passive"))
      (node (ref "U1") (pin "13") (pinfunction "PF3_13") (pintype "passive"))
    )
    (net (code "89") (name "/PF4") (class "Default")
      (node (ref "P2") (pin "12") (pinfunction "12_12") (pintype "passive"))
      (node (ref "U1") (pin "14") (pinfunction "PF4_14") (pintype "passive"))
    )
    (net (code "90") (name "/PF5") (class "Default")
      (node (ref "P2") (pin "11") (pinfunction "11_11") (pintype "passive"))
      (node (ref "U1") (pin "15") (pinfunction "PF5_15") (pintype "passive"))
    )
    (net (code "91") (name "/PF6") (class "Default")
      (node (ref "P2") (pin "14") (pinfunction "14_14") (pintype "passive"))
      (node (ref "U1") (pin "18") (pinfunction "PF6/ADC3_IN4_18") (pintype "passive"))
    )
    (net (code "92") (name "/PF7") (class "Default")
      (node (ref "P2") (pin "13") (pinfunction "13_13") (pintype "passive"))
      (node (ref "U1") (pin "19") (pinfunction "PF7/ADC3_IN5_19") (pintype "passive"))
    )
    (net (code "93") (name "/PF8") (class "Default")
      (node (ref "P2") (pin "16") (pinfunction "16_16") (pintype "passive"))
      (node (ref "U1") (pin "20") (pinfunction "PF8/ADC3_IN6_20") (pintype "passive"))
    )
    (net (code "94") (name "/PF9") (class "Default")
      (node (ref "P2") (pin "15") (pinfunction "15_15") (pintype "passive"))
      (node (ref "U1") (pin "21") (pinfunction "PF9/ADC3_IN7_21") (pintype "passive"))
    )
    (net (code "95") (name "/PF10") (class "Default")
      (node (ref "P2") (pin "18") (pinfunction "18_18") (pintype "passive"))
      (node (ref "U1") (pin "22") (pinfunction "PF10/ADC3_IN8_22") (pintype "passive"))
    )
    (net (code "96") (name "/PF11") (class "Default")
      (node (ref "P1") (pin "9") (pinfunction "9_9") (pintype "passive"))
      (node (ref "U1") (pin "49") (pinfunction "PF11_49") (pintype "passive"))
    )
    (net (code "97") (name "/PF12") (class "Default")
      (node (ref "P1") (pin "12") (pinfunction "12_12") (pintype "passive"))
      (node (ref "U1") (pin "50") (pinfunction "PF12_50") (pintype "passive"))
    )
    (net (code "98") (name "/PF13") (class "Default")
      (node (ref "P1") (pin "11") (pinfunction "11_11") (pintype "passive"))
      (node (ref "U1") (pin "53") (pinfunction "PF13_53") (pintype "passive"))
    )
    (net (code "99") (name "/PF14") (class "Default")
      (node (ref "P1") (pin "14") (pinfunction "14_14") (pintype "passive"))
      (node (ref "U1") (pin "54") (pinfunction "PF14_54") (pintype "passive"))
    )
    (net (code "100") (name "/PF15") (class "Default")
      (node (ref "U1") (pin "55") (pinfunction "PF15_55") (pintype "passive"))
    )
    (net (code "101") (name "/PG0") (class "Default")
      (node (ref "P1") (pin "13") (pinfunction "13_13") (pintype "passive"))
      (node (ref "U1") (pin "56") (pinfunction "PG0_56") (pintype "passive"))
    )
    (net (code "102") (name "/PG1") (class "Default")
      (node (ref "P1") (pin "16") (pinfunction "16_16") (pintype "passive"))
      (node (ref "U1") (pin "57") (pinfunction "PG1_57") (pintype "passive"))
    )
    (net (code "103") (name "/PG2") (class "Default")
      (node (ref "P3") (pin "16") (pinfunction "16_16") (pintype "passive"))
      (node (ref "U1") (pin "87") (pinfunction "PG2_87") (pintype "passive"))
    )
    (net (code "104") (name "/PG3") (class "Default")
      (node (ref "P3") (pin "15") (pinfunction "15_15") (pintype "passive"))
      (node (ref "U1") (pin "88") (pinfunction "PG3_88") (pintype "passive"))
    )
    (net (code "105") (name "/PG4") (class "Default")
      (node (ref "P3") (pin "14") (pinfunction "14_14") (pintype "passive"))
      (node (ref "U1") (pin "89") (pinfunction "PG4_89") (pintype "passive"))
    )
    (net (code "106") (name "/PG5") (class "Default")
      (node (ref "P3") (pin "13") (pinfunction "13_13") (pintype "passive"))
      (node (ref "U1") (pin "90") (pinfunction "PG5_90") (pintype "passive"))
    )
    (net (code "107") (name "/PG6") (class "Default")
      (node (ref "P3") (pin "12") (pinfunction "12_12") (pintype "passive"))
      (node (ref "U1") (pin "91") (pinfunction "PG6_91") (pintype "passive"))
    )
    (net (code "108") (name "/PG7") (class "Default")
      (node (ref "P3") (pin "11") (pinfunction "11_11") (pintype "passive"))
      (node (ref "U1") (pin "92") (pinfunction "PG7_92") (pintype "passive"))
    )
    (net (code "109") (name "/PG8") (class "Default")
      (node (ref "P3") (pin "10") (pinfunction "10_10") (pintype "passive"))
      (node (ref "U1") (pin "93") (pinfunction "PG8_93") (pintype "passive"))
    )
    (net (code "110") (name "/PG9") (class "Default")
      (node (ref "P4") (pin "15") (pinfunction "15_15") (pintype "passive"))
      (node (ref "U1") (pin "124") (pinfunction "PG9_124") (pintype "passive"))
    )
    (net (code "111") (name "/PG10") (class "Default")
      (node (ref "OLED1") (pin "6") (pinfunction "DC_6") (pintype "passive"))
      (node (ref "P4") (pin "16") (pinfunction "16_16") (pintype "passive"))
      (node (ref "U1") (pin "125") (pinfunction "PG10_125") (pintype "passive"))
    )
    (net (code "112") (name "/PG11") (class "Default")
      (node (ref "P4") (pin "13") (pinfunction "13_13") (pintype "passive"))
      (node (ref "U1") (pin "126") (pinfunction "PG11_126") (pintype "passive"))
    )
    (net (code "113") (name "/PG12") (class "Default")
      (node (ref "OLED1") (pin "5") (pinfunction "RES_5") (pintype "passive"))
      (node (ref "P4") (pin "14") (pinfunction "14_14") (pintype "passive"))
      (node (ref "U1") (pin "127") (pinfunction "PG12_127") (pintype "passive"))
    )
    (net (code "114") (name "/PG13") (class "Default")
      (node (ref "P4") (pin "11") (pinfunction "11_11") (pintype "passive"))
      (node (ref "U1") (pin "128") (pinfunction "PG13_128") (pintype "passive"))
    )
    (net (code "115") (name "/PG14") (class "Default")
      (node (ref "OLED1") (pin "4") (pinfunction "D1/SDA_4") (pintype "passive"))
      (node (ref "P4") (pin "12") (pinfunction "12_12") (pintype "passive"))
      (node (ref "U1") (pin "129") (pinfunction "PG14_129") (pintype "passive"))
    )
    (net (code "116") (name "/PG15") (class "Default")
      (node (ref "P4") (pin "9") (pinfunction "9_9") (pintype "passive"))
      (node (ref "U1") (pin "132") (pinfunction "PG15_132") (pintype "passive"))
    )
    (net (code "117") (name "/REST") (class "Default")
      (node (ref "C14") (pin "1") (pinfunction "1_1") (pintype "passive"))
      (node (ref "R5") (pin "1") (pinfunction "1_1") (pintype "passive"))
      (node (ref "S2") (pin "1") (pinfunction "1_1") (pintype "passive"))
      (node (ref "U1") (pin "25") (pinfunction "NRST_25") (pintype "passive"))
    )
    (net (code "118") (name "/RXD") (class "Default")
      (node (ref "P3") (pin "4") (pinfunction "4_4") (pintype "passive"))
      (node (ref "R1") (pin "1") (pinfunction "1_1") (pintype "passive"))
      (node (ref "U1") (pin "101") (pinfunction "PA9/USART1_TX_101") (pintype "passive"))
    )
    (net (code "119") (name "/SWCLK") (class "Default")
      (node (ref "D3") (pin "2") (pinfunction "K_2") (pintype "passive"))
      (node (ref "P6") (pin "1") (pinfunction "1_1") (pintype "passive"))
      (node (ref "U1") (pin "109") (pinfunction "PA14/JTCK_SWCLK_109") (pintype "passive"))
    )
    (net (code "120") (name "/SWDIO") (class "Default")
      (node (ref "P6") (pin "2") (pinfunction "2_2") (pintype "passive"))
      (node (ref "U1") (pin "105") (pinfunction "PA13/JTMS_SWDIO_105") (pintype "passive"))
    )
    (net (code "121") (name "/TXD") (class "Default")
      (node (ref "D1") (pin "2") (pinfunction "K_2") (pintype "passive"))
      (node (ref "P3") (pin "3") (pinfunction "3_3") (pintype "passive"))
      (node (ref "U1") (pin "102") (pinfunction "PA10/USART1_RX_102") (pintype "passive"))
    )
    (net (code "122") (name "DC_IN") (class "Default")
      (node (ref "C6") (pin "1") (pinfunction "1_1") (pintype "passive"))
      (node (ref "C8") (pin "2") (pinfunction "2_2") (pintype "passive"))
      (node (ref "S1") (pin "2") (pinfunction "NO_2") (pintype "passive"))
      (node (ref "U3") (pin "3") (pinfunction "IN_3") (pintype "passive"))
    )
    (net (code "123") (name "GND") (class "Default")
      (node (ref "C1") (pin "2") (pinfunction "2_2") (pintype "passive"))
      (node (ref "C10") (pin "1") (pinfunction "1_1") (pintype "passive"))
      (node (ref "C11") (pin "2") (pinfunction "2_2") (pintype "passive"))
      (node (ref "C12") (pin "1") (pinfunction "1_1") (pintype "passive"))
      (node (ref "C13") (pin "1") (pinfunction "1_1") (pintype "passive"))
      (node (ref "C14") (pin "2") (pinfunction "2_2") (pintype "passive"))
      (node (ref "C15") (pin "1") (pinfunction "1_1") (pintype "passive"))
      (node (ref "C16") (pin "1") (pinfunction "1_1") (pintype "passive"))
      (node (ref "C17") (pin "1") (pinfunction "1_1") (pintype "passive"))
      (node (ref "C18") (pin "1") (pinfunction "1_1") (pintype "passive"))
      (node (ref "C19") (pin "1") (pinfunction "1_1") (pintype "passive"))
      (node (ref "C2") (pin "2") (pinfunction "2_2") (pintype "passive"))
      (node (ref "C20") (pin "1") (pinfunction "1_1") (pintype "passive"))
      (node (ref "C21") (pin "1") (pinfunction "1_1") (pintype "passive"))
      (node (ref "C22") (pin "1") (pinfunction "1_1") (pintype "passive"))
      (node (ref "C23") (pin "1") (pinfunction "1_1") (pintype "passive"))
      (node (ref "C24") (pin "1") (pinfunction "1_1") (pintype "passive"))
      (node (ref "C27") (pin "1") (pinfunction "1_1") (pintype "passive"))
      (node (ref "C3") (pin "2") (pinfunction "2_2") (pintype "passive"))
      (node (ref "C4") (pin "2") (pinfunction "2_2") (pintype "passive"))
      (node (ref "C5") (pin "2") (pinfunction "2_2") (pintype "passive"))
      (node (ref "C6") (pin "2") (pinfunction "2_2") (pintype "passive"))
      (node (ref "C7") (pin "1") (pinfunction "1_1") (pintype "passive"))
      (node (ref "C8") (pin "1") (pinfunction "1_1") (pintype "passive"))
      (node (ref "C9") (pin "2") (pinfunction "2_2") (pintype "passive"))
      (node (ref "D2") (pin "2") (pinfunction "K_2") (pintype "passive"))
      (node (ref "J1") (pin "5") (pinfunction "VSS_5") (pintype "passive"))
      (node (ref "OLED1") (pin "1") (pinfunction "GND_1") (pintype "passive"))
      (node (ref "OLED1") (pin "7") (pinfunction "CS_7") (pintype "passive"))
      (node (ref "P5") (pin "2") (pinfunction "2_2") (pintype "passive"))
      (node (ref "P5") (pin "4") (pinfunction "4_4") (pintype "passive"))
      (node (ref "P6") (pin "4") (pinfunction "4_4") (pintype "passive"))
      (node (ref "S2") (pin "2") (pinfunction "2_2") (pintype "passive"))
      (node (ref "S3") (pin "3") (pinfunction "B2_3") (pintype "passive"))
      (node (ref "S3") (pin "4") (pinfunction "B1_4") (pintype "passive"))
      (node (ref "U1") (pin "107") (pinfunction "VSS2_107") (pintype "passive"))
      (node (ref "U1") (pin "120") (pinfunction "VSS10_120") (pintype "passive"))
      (node (ref "U1") (pin "130") (pinfunction "VSS11_130") (pintype "passive"))
      (node (ref "U1") (pin "143") (pinfunction "VSS3_143") (pintype "passive"))
      (node (ref "U1") (pin "16") (pinfunction "VSS5_16") (pintype "passive"))
      (node (ref "U1") (pin "30") (pinfunction "VSSA_30") (pintype "passive"))
      (node (ref "U1") (pin "31") (pinfunction "Vref-_31") (pintype "passive"))
      (node (ref "U1") (pin "38") (pinfunction "VSS4_38") (pintype "passive"))
      (node (ref "U1") (pin "51") (pinfunction "VSS6_51") (pintype "passive"))
      (node (ref "U1") (pin "61") (pinfunction "VSS7_61") (pintype "passive"))
      (node (ref "U1") (pin "71") (pinfunction "VSS1_71") (pintype "passive"))
      (node (ref "U1") (pin "83") (pinfunction "VSS8_83") (pintype "passive"))
      (node (ref "U1") (pin "94") (pinfunction "VSS9_94") (pintype "passive"))
      (node (ref "U2") (pin "1") (pinfunction "GND_1") (pintype "passive"))
      (node (ref "U3") (pin "1") (pinfunction "GND_1") (pintype "passive"))
    )
    (net (code "124") (name "Net-(D2-A)") (class "Default")
      (node (ref "D2") (pin "1") (pinfunction "A_1") (pintype "passive"))
      (node (ref "R2") (pin "2") (pinfunction "2_2") (pintype "passive"))
    )
    (net (code "125") (name "Net-(D3-A)") (class "Default")
      (node (ref "D3") (pin "1") (pinfunction "A_1") (pintype "passive"))
      (node (ref "R6") (pin "2") (pinfunction "2_2") (pintype "passive"))
    )
    (net (code "126") (name "Net-(U1-OSC_IN)") (class "Default")
      (node (ref "C9") (pin "1") (pinfunction "1_1") (pintype "passive"))
      (node (ref "R3") (pin "2") (pinfunction "2_2") (pintype "passive"))
      (node (ref "U1") (pin "23") (pinfunction "OSC_IN_23") (pintype "passive"))
      (node (ref "Y2") (pin "1") (pinfunction "OSC1_1") (pintype "passive"))
    )
    (net (code "127") (name "Net-(U1-OSC_OUT)") (class "Default")
      (node (ref "C11") (pin "1") (pinfunction "1_1") (pintype "passive"))
      (node (ref "R3") (pin "1") (pinfunction "1_1") (pintype "passive"))
      (node (ref "U1") (pin "24") (pinfunction "OSC_OUT_24") (pintype "passive"))
      (node (ref "Y2") (pin "2") (pinfunction "OSC2_2") (pintype "passive"))
    )
    (net (code "128") (name "Net-(U1-VDDA)") (class "Default")
      (node (ref "C12") (pin "2") (pinfunction "2_2") (pintype "passive"))
      (node (ref "C13") (pin "2") (pinfunction "2_2") (pintype "passive"))
      (node (ref "R4") (pin "2") (pinfunction "2_2") (pintype "passive"))
      (node (ref "U1") (pin "32") (pinfunction "Vref+_32") (pintype "passive"))
      (node (ref "U1") (pin "33") (pinfunction "VDDA_33") (pintype "passive"))
    )
    (net (code "129") (name "Net-(U2-V3)") (class "Default")
      (node (ref "C1") (pin "1") (pinfunction "1_1") (pintype "passive"))
      (node (ref "U2") (pin "4") (pinfunction "V3_4") (pintype "passive"))
    )
    (net (code "130") (name "POWER") (class "Default")
      (node (ref "C2") (pin "1") (pinfunction "1_1") (pintype "passive"))
      (node (ref "J1") (pin "1") (pinfunction "VCC_1") (pintype "passive"))
      (node (ref "S1") (pin "1") (pinfunction "COMMON_1") (pintype "passive"))
      (node (ref "U2") (pin "16") (pinfunction "VCC_16") (pintype "passive"))
    )
    (net (code "131") (name "unconnected-(J1-ID-Pad4)") (class "Default")
      (node (ref "J1") (pin "4") (pinfunction "ID_4") (pintype "passive"))
    )
    (net (code "132") (name "unconnected-(U1-NC-Pad106)") (class "Default")
      (node (ref "U1") (pin "106") (pinfunction "NC_106") (pintype "passive"))
    )
    (net (code "133") (name "unconnected-(U2-CTS-Pad9)") (class "Default")
      (node (ref "U2") (pin "9") (pinfunction "CTS_9") (pintype "passive"))
    )
    (net (code "134") (name "unconnected-(U2-DCD-Pad12)") (class "Default")
      (node (ref "U2") (pin "12") (pinfunction "DCD_12") (pintype "passive"))
    )
    (net (code "135") (name "unconnected-(U2-DSR-Pad10)") (class "Default")
      (node (ref "U2") (pin "10") (pinfunction "DSR_10") (pintype "passive"))
    )
    (net (code "136") (name "unconnected-(U2-DTR-Pad13)") (class "Default")
      (node (ref "U2") (pin "13") (pinfunction "DTR_13") (pintype "passive"))
    )
    (net (code "137") (name "unconnected-(U2-RI-Pad11)") (class "Default")
      (node (ref "U2") (pin "11") (pinfunction "RI_11") (pintype "passive"))
    )
    (net (code "138") (name "unconnected-(U2-RS232-Pad15)") (class "Default")
      (node (ref "U2") (pin "15") (pinfunction "RS232_15") (pintype "passive"))
    )
    (net (code "139") (name "unconnected-(U2-RTS-Pad14)") (class "Default")
      (node (ref "U2") (pin "14") (pinfunction "RTS_14") (pintype "passive"))
    )
  )
)
